# js_simple.net
KiCad netlist of a schematic drawn in EAGLE
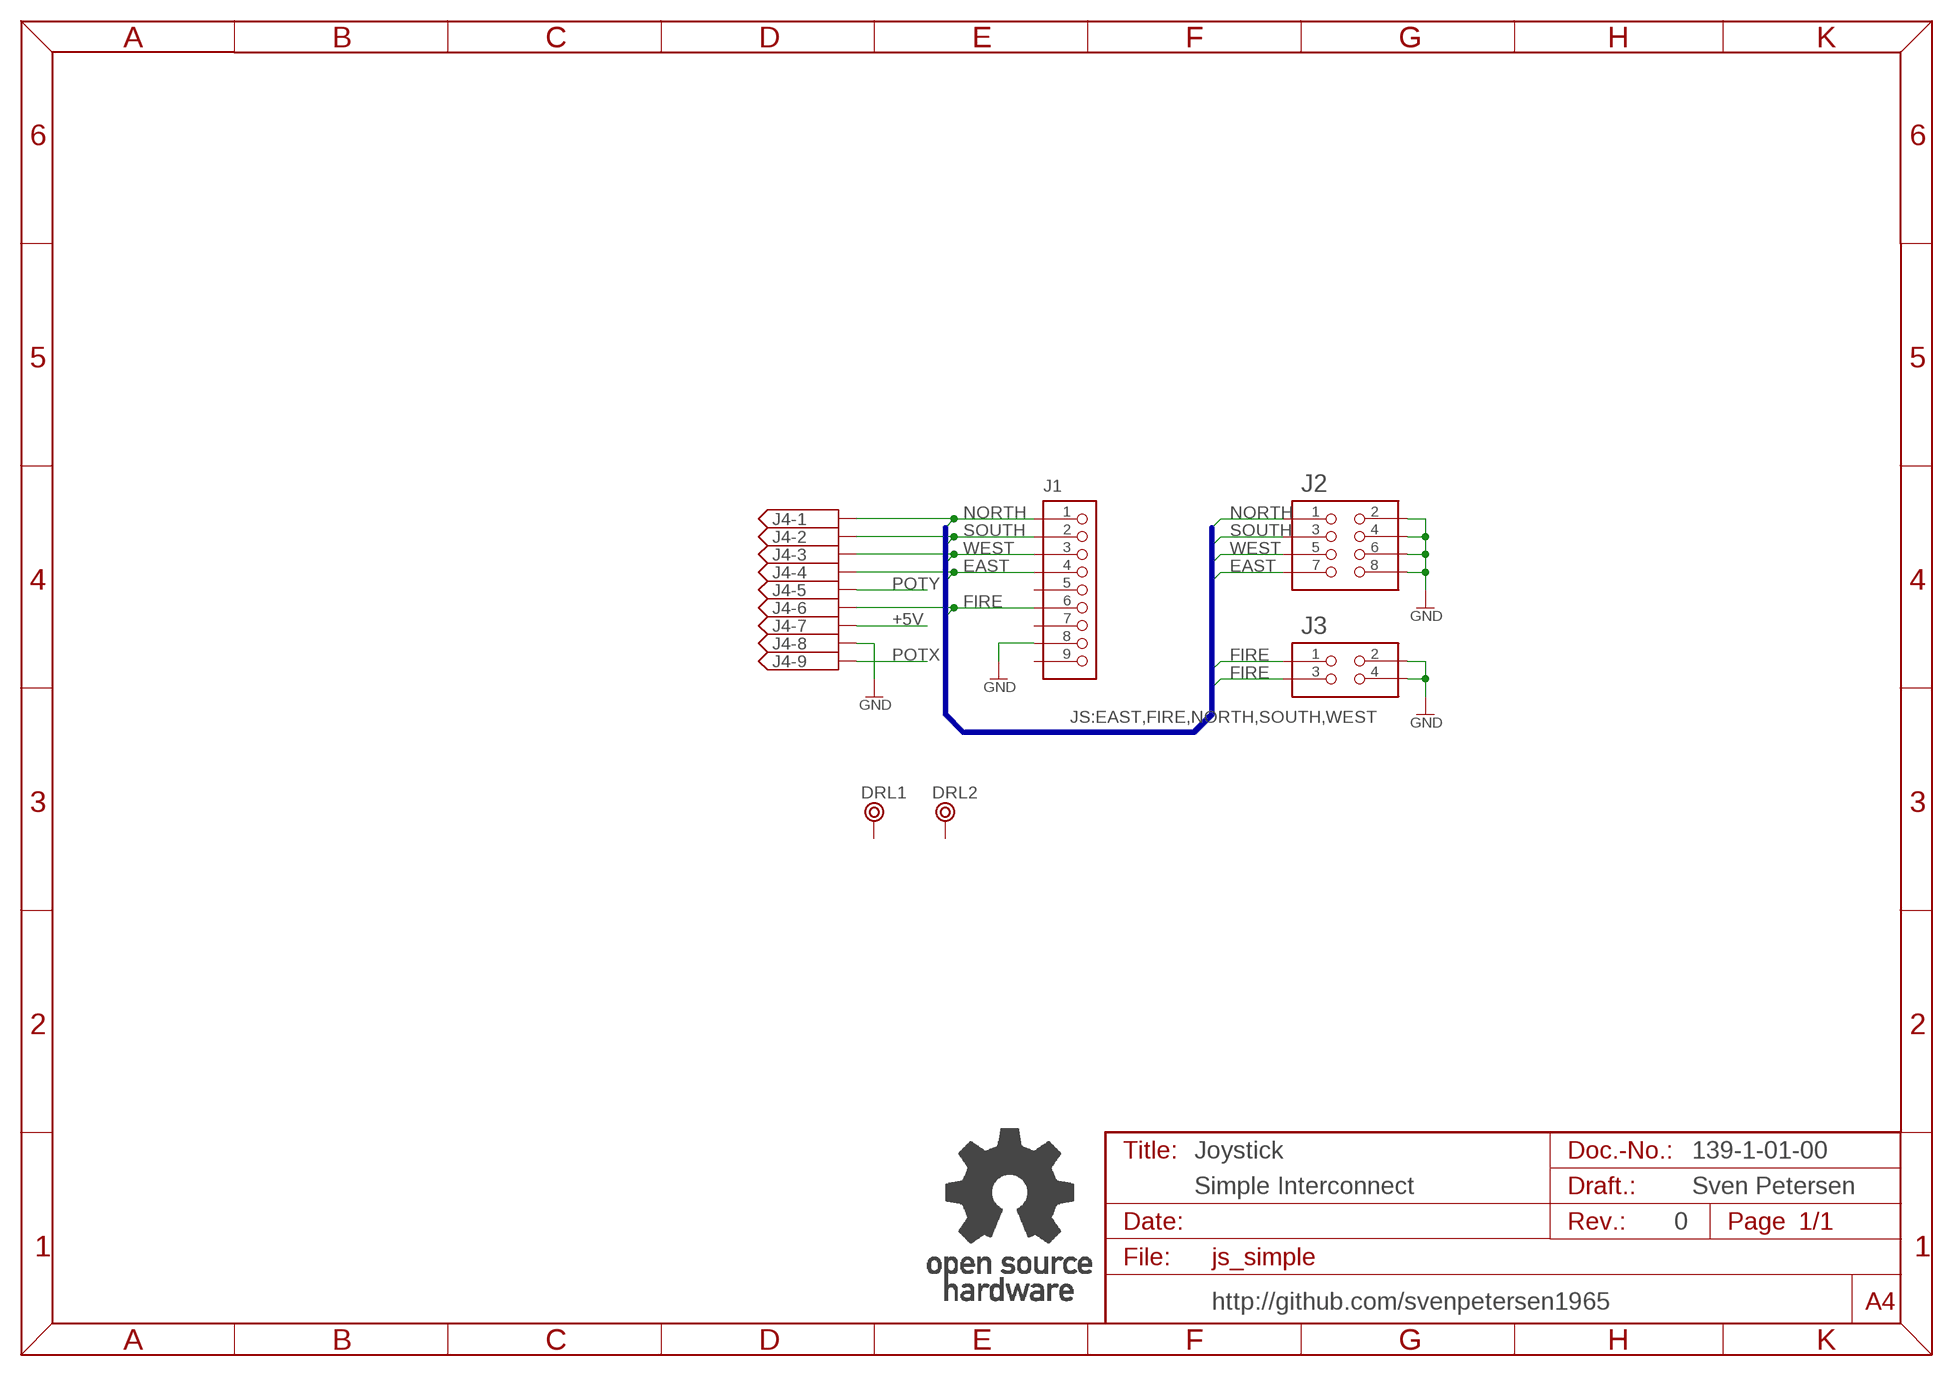
[diagram p0: schematic, sheet 1]

(export (version "E")
  (design (tool "Eeschema 10.0.6"))
  (components
    (comp (ref "DRL1")
      (value "BOHR3,5")
      (footprint "eagle-import:BOHR3,5")
      (libsource (lib "eagle-import") (part "BOHR3,5"))
    )
    (comp (ref "DRL2")
      (value "BOHR3,5")
      (footprint "eagle-import:BOHR3,5")
      (libsource (lib "eagle-import") (part "BOHR3,5"))
    )
    (comp (ref "J1")
      (value "PINHD-1X9")
      (footprint "eagle-import:1X09")
      (libsource (lib "eagle-import") (part "PINHD-1X9"))
    )
    (comp (ref "J2")
      (value "PINHD-2X4")
      (footprint "eagle-import:2X04")
      (libsource (lib "eagle-import") (part "PINHD-2X4"))
    )
    (comp (ref "J3")
      (value "PINHD-2X2")
      (footprint "eagle-import:2X02")
      (libsource (lib "eagle-import") (part "PINHD-2X2"))
    )
    (comp (ref "J4")
      (value "9X1X2SMD")
      (footprint "eagle-import:9PIN_1X2SMD")
      (libsource (lib "eagle-import") (part "9X1X2SMD"))
    )
    (comp (ref "U$8")
      (value "OPEN_SOURCE_HW")
      (footprint "eagle-import:OPENHW")
      (libsource (lib "eagle-import") (part "OPEN_SOURCE_HW"))
    )
  )
  (nets
    (net (code "2") (name "/+5V") (class "Default")
      (node (ref "J4") (pin "7") (pinfunction "1_7") (pintype "passive"))
    )
    (net (code "3") (name "/EAST") (class "Default")
      (node (ref "J1") (pin "4") (pinfunction "4_4") (pintype "passive"))
      (node (ref "J2") (pin "7") (pinfunction "7_7") (pintype "passive"))
      (node (ref "J4") (pin "4") (pinfunction "1_4") (pintype "passive"))
    )
    (net (code "4") (name "/FIRE") (class "Default")
      (node (ref "J1") (pin "6") (pinfunction "6_6") (pintype "passive"))
      (node (ref "J3") (pin "1") (pinfunction "1_1") (pintype "passive"))
      (node (ref "J3") (pin "3") (pinfunction "3_3") (pintype "passive"))
      (node (ref "J4") (pin "6") (pinfunction "1_6") (pintype "passive"))
    )
    (net (code "5") (name "/NORTH") (class "Default")
      (node (ref "J1") (pin "1") (pinfunction "1_1") (pintype "passive"))
      (node (ref "J2") (pin "1") (pinfunction "1_1") (pintype "passive"))
      (node (ref "J4") (pin "1") (pinfunction "1_1") (pintype "passive"))
    )
    (net (code "6") (name "/POTX") (class "Default")
      (node (ref "J4") (pin "9") (pinfunction "1_9") (pintype "passive"))
    )
    (net (code "7") (name "/POTY") (class "Default")
      (node (ref "J4") (pin "5") (pinfunction "1_5") (pintype "passive"))
    )
    (net (code "8") (name "/SOUTH") (class "Default")
      (node (ref "J1") (pin "2") (pinfunction "2_2") (pintype "passive"))
      (node (ref "J2") (pin "3") (pinfunction "3_3") (pintype "passive"))
      (node (ref "J4") (pin "2") (pinfunction "1_2") (pintype "passive"))
    )
    (net (code "9") (name "/WEST") (class "Default")
      (node (ref "J1") (pin "3") (pinfunction "3_3") (pintype "passive"))
      (node (ref "J2") (pin "5") (pinfunction "5_5") (pintype "passive"))
      (node (ref "J4") (pin "3") (pinfunction "1_3") (pintype "passive"))
    )
    (net (code "11") (name "GND") (class "Default")
      (node (ref "J1") (pin "8") (pinfunction "8_8") (pintype "passive"))
      (node (ref "J2") (pin "2") (pinfunction "2_2") (pintype "passive"))
      (node (ref "J2") (pin "4") (pinfunction "4_4") (pintype "passive"))
      (node (ref "J2") (pin "6") (pinfunction "6_6") (pintype "passive"))
      (node (ref "J2") (pin "8") (pinfunction "8_8") (pintype "passive"))
      (node (ref "J3") (pin "2") (pinfunction "2_2") (pintype "passive"))
      (node (ref "J3") (pin "4") (pinfunction "4_4") (pintype "passive"))
      (node (ref "J4") (pin "8") (pinfunction "1_8") (pintype "passive"))
    )
    (net (code "12") (name "unconnected-(DRL1-PadP$1)") (class "Default")
      (node (ref "DRL1") (pin "P$1") (pinfunction "P$1_P$1") (pintype "passive"))
    )
    (net (code "13") (name "unconnected-(DRL2-PadP$1)") (class "Default")
      (node (ref "DRL2") (pin "P$1") (pinfunction "P$1_P$1") (pintype "passive"))
    )
    (net (code "14") (name "unconnected-(J1-Pad5)") (class "Default")
      (node (ref "J1") (pin "5") (pinfunction "5_5") (pintype "passive"))
    )
    (net (code "15") (name "unconnected-(J1-Pad7)") (class "Default")
      (node (ref "J1") (pin "7") (pinfunction "7_7") (pintype "passive"))
    )
    (net (code "16") (name "unconnected-(J1-Pad9)") (class "Default")
      (node (ref "J1") (pin "9") (pinfunction "9_9") (pintype "passive"))
    )
  )
)
